# 4_-_Output.net
KiCad netlist of a schematic drawn in Altium Designer
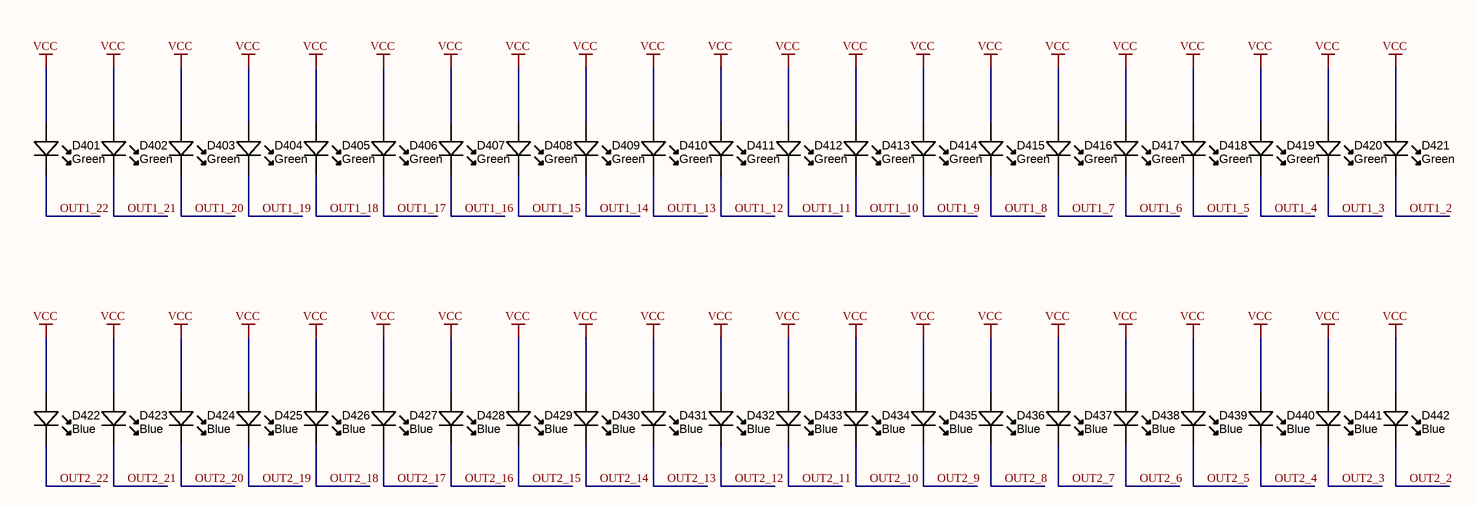
[diagram p0: 4 - Output.SchDoc]

(export (version "E")
  (design (tool "Eeschema 10.0.6"))
  (components
    (comp (ref "D401")
      (value "Green")
      (footprint "LED-0805S-SIDELED-2.1X0.6X1.0")
      (description "LED 0805 SIDELED SMD Green 250mcd 525nm")
      (fields (field (name "COLOR") "Green"))
      (libsource (lib "PBL - Light Sources") (part "LED_SMD_PureGreen_0805RA_250mcd"))
    )
    (comp (ref "D402")
      (value "Green")
      (footprint "LED-0805S-SIDELED-2.1X0.6X1.0")
      (description "LED 0805 SIDELED SMD Green 250mcd 525nm")
      (fields (field (name "COLOR") "Green"))
      (libsource (lib "PBL - Light Sources") (part "LED_SMD_PureGreen_0805RA_250mcd"))
    )
    (comp (ref "D403")
      (value "Green")
      (footprint "LED-0805S-SIDELED-2.1X0.6X1.0")
      (description "LED 0805 SIDELED SMD Green 250mcd 525nm")
      (fields (field (name "COLOR") "Green"))
      (libsource (lib "PBL - Light Sources") (part "LED_SMD_PureGreen_0805RA_250mcd"))
    )
    (comp (ref "D404")
      (value "Green")
      (footprint "LED-0805S-SIDELED-2.1X0.6X1.0")
      (description "LED 0805 SIDELED SMD Green 250mcd 525nm")
      (fields (field (name "COLOR") "Green"))
      (libsource (lib "PBL - Light Sources") (part "LED_SMD_PureGreen_0805RA_250mcd"))
    )
    (comp (ref "D405")
      (value "Green")
      (footprint "LED-0805S-SIDELED-2.1X0.6X1.0")
      (description "LED 0805 SIDELED SMD Green 250mcd 525nm")
      (fields (field (name "COLOR") "Green"))
      (libsource (lib "PBL - Light Sources") (part "LED_SMD_PureGreen_0805RA_250mcd"))
    )
    (comp (ref "D406")
      (value "Green")
      (footprint "LED-0805S-SIDELED-2.1X0.6X1.0")
      (description "LED 0805 SIDELED SMD Green 250mcd 525nm")
      (fields (field (name "COLOR") "Green"))
      (libsource (lib "PBL - Light Sources") (part "LED_SMD_PureGreen_0805RA_250mcd"))
    )
    (comp (ref "D407")
      (value "Green")
      (footprint "LED-0805S-SIDELED-2.1X0.6X1.0")
      (description "LED 0805 SIDELED SMD Green 250mcd 525nm")
      (fields (field (name "COLOR") "Green"))
      (libsource (lib "PBL - Light Sources") (part "LED_SMD_PureGreen_0805RA_250mcd"))
    )
    (comp (ref "D408")
      (value "Green")
      (footprint "LED-0805S-SIDELED-2.1X0.6X1.0")
      (description "LED 0805 SIDELED SMD Green 250mcd 525nm")
      (fields (field (name "COLOR") "Green"))
      (libsource (lib "PBL - Light Sources") (part "LED_SMD_PureGreen_0805RA_250mcd"))
    )
    (comp (ref "D409")
      (value "Green")
      (footprint "LED-0805S-SIDELED-2.1X0.6X1.0")
      (description "LED 0805 SIDELED SMD Green 250mcd 525nm")
      (fields (field (name "COLOR") "Green"))
      (libsource (lib "PBL - Light Sources") (part "LED_SMD_PureGreen_0805RA_250mcd"))
    )
    (comp (ref "D410")
      (value "Green")
      (footprint "LED-0805S-SIDELED-2.1X0.6X1.0")
      (description "LED 0805 SIDELED SMD Green 250mcd 525nm")
      (fields (field (name "COLOR") "Green"))
      (libsource (lib "PBL - Light Sources") (part "LED_SMD_PureGreen_0805RA_250mcd"))
    )
    (comp (ref "D411")
      (value "Green")
      (footprint "LED-0805S-SIDELED-2.1X0.6X1.0")
      (description "LED 0805 SIDELED SMD Green 250mcd 525nm")
      (fields (field (name "COLOR") "Green"))
      (libsource (lib "PBL - Light Sources") (part "LED_SMD_PureGreen_0805RA_250mcd"))
    )
    (comp (ref "D412")
      (value "Green")
      (footprint "LED-0805S-SIDELED-2.1X0.6X1.0")
      (description "LED 0805 SIDELED SMD Green 250mcd 525nm")
      (fields (field (name "COLOR") "Green"))
      (libsource (lib "PBL - Light Sources") (part "LED_SMD_PureGreen_0805RA_250mcd"))
    )
    (comp (ref "D413")
      (value "Green")
      (footprint "LED-0805S-SIDELED-2.1X0.6X1.0")
      (description "LED 0805 SIDELED SMD Green 250mcd 525nm")
      (fields (field (name "COLOR") "Green"))
      (libsource (lib "PBL - Light Sources") (part "LED_SMD_PureGreen_0805RA_250mcd"))
    )
    (comp (ref "D414")
      (value "Green")
      (footprint "LED-0805S-SIDELED-2.1X0.6X1.0")
      (description "LED 0805 SIDELED SMD Green 250mcd 525nm")
      (fields (field (name "COLOR") "Green"))
      (libsource (lib "PBL - Light Sources") (part "LED_SMD_PureGreen_0805RA_250mcd"))
    )
    (comp (ref "D415")
      (value "Green")
      (footprint "LED-0805S-SIDELED-2.1X0.6X1.0")
      (description "LED 0805 SIDELED SMD Green 250mcd 525nm")
      (fields (field (name "COLOR") "Green"))
      (libsource (lib "PBL - Light Sources") (part "LED_SMD_PureGreen_0805RA_250mcd"))
    )
    (comp (ref "D416")
      (value "Green")
      (footprint "LED-0805S-SIDELED-2.1X0.6X1.0")
      (description "LED 0805 SIDELED SMD Green 250mcd 525nm")
      (fields (field (name "COLOR") "Green"))
      (libsource (lib "PBL - Light Sources") (part "LED_SMD_PureGreen_0805RA_250mcd"))
    )
    (comp (ref "D417")
      (value "Green")
      (footprint "LED-0805S-SIDELED-2.1X0.6X1.0")
      (description "LED 0805 SIDELED SMD Green 250mcd 525nm")
      (fields (field (name "COLOR") "Green"))
      (libsource (lib "PBL - Light Sources") (part "LED_SMD_PureGreen_0805RA_250mcd"))
    )
    (comp (ref "D418")
      (value "Green")
      (footprint "LED-0805S-SIDELED-2.1X0.6X1.0")
      (description "LED 0805 SIDELED SMD Green 250mcd 525nm")
      (fields (field (name "COLOR") "Green"))
      (libsource (lib "PBL - Light Sources") (part "LED_SMD_PureGreen_0805RA_250mcd"))
    )
    (comp (ref "D419")
      (value "Green")
      (footprint "LED-0805S-SIDELED-2.1X0.6X1.0")
      (description "LED 0805 SIDELED SMD Green 250mcd 525nm")
      (fields (field (name "COLOR") "Green"))
      (libsource (lib "PBL - Light Sources") (part "LED_SMD_PureGreen_0805RA_250mcd"))
    )
    (comp (ref "D420")
      (value "Green")
      (footprint "LED-0805S-SIDELED-2.1X0.6X1.0")
      (description "LED 0805 SIDELED SMD Green 250mcd 525nm")
      (fields (field (name "COLOR") "Green"))
      (libsource (lib "PBL - Light Sources") (part "LED_SMD_PureGreen_0805RA_250mcd"))
    )
    (comp (ref "D421")
      (value "Green")
      (footprint "LED-0805S-SIDELED-2.1X0.6X1.0")
      (description "LED 0805 SIDELED SMD Green 250mcd 525nm")
      (fields (field (name "COLOR") "Green"))
      (libsource (lib "PBL - Light Sources") (part "LED_SMD_PureGreen_0805RA_250mcd"))
    )
    (comp (ref "D422")
      (value "Blue")
      (footprint "LED-0805S-SIDELED-2.1X0.6X1.0")
      (description "LED 0805 SIDELED SMD Green 250mcd 525nm")
      (fields (field (name "COLOR") "Blue"))
      (libsource (lib "PBL - Light Sources") (part "LED_SMD_PureGreen_0805RA_250mcd"))
    )
    (comp (ref "D423")
      (value "Blue")
      (footprint "LED-0805S-SIDELED-2.1X0.6X1.0")
      (description "LED 0805 SIDELED SMD Green 250mcd 525nm")
      (fields (field (name "COLOR") "Blue"))
      (libsource (lib "PBL - Light Sources") (part "LED_SMD_PureGreen_0805RA_250mcd"))
    )
    (comp (ref "D424")
      (value "Blue")
      (footprint "LED-0805S-SIDELED-2.1X0.6X1.0")
      (description "LED 0805 SIDELED SMD Green 250mcd 525nm")
      (fields (field (name "COLOR") "Blue"))
      (libsource (lib "PBL - Light Sources") (part "LED_SMD_PureGreen_0805RA_250mcd"))
    )
    (comp (ref "D425")
      (value "Blue")
      (footprint "LED-0805S-SIDELED-2.1X0.6X1.0")
      (description "LED 0805 SIDELED SMD Green 250mcd 525nm")
      (fields (field (name "COLOR") "Blue"))
      (libsource (lib "PBL - Light Sources") (part "LED_SMD_PureGreen_0805RA_250mcd"))
    )
    (comp (ref "D426")
      (value "Blue")
      (footprint "LED-0805S-SIDELED-2.1X0.6X1.0")
      (description "LED 0805 SIDELED SMD Green 250mcd 525nm")
      (fields (field (name "COLOR") "Blue"))
      (libsource (lib "PBL - Light Sources") (part "LED_SMD_PureGreen_0805RA_250mcd"))
    )
    (comp (ref "D427")
      (value "Blue")
      (footprint "LED-0805S-SIDELED-2.1X0.6X1.0")
      (description "LED 0805 SIDELED SMD Green 250mcd 525nm")
      (fields (field (name "COLOR") "Blue"))
      (libsource (lib "PBL - Light Sources") (part "LED_SMD_PureGreen_0805RA_250mcd"))
    )
    (comp (ref "D428")
      (value "Blue")
      (footprint "LED-0805S-SIDELED-2.1X0.6X1.0")
      (description "LED 0805 SIDELED SMD Green 250mcd 525nm")
      (fields (field (name "COLOR") "Blue"))
      (libsource (lib "PBL - Light Sources") (part "LED_SMD_PureGreen_0805RA_250mcd"))
    )
    (comp (ref "D429")
      (value "Blue")
      (footprint "LED-0805S-SIDELED-2.1X0.6X1.0")
      (description "LED 0805 SIDELED SMD Green 250mcd 525nm")
      (fields (field (name "COLOR") "Blue"))
      (libsource (lib "PBL - Light Sources") (part "LED_SMD_PureGreen_0805RA_250mcd"))
    )
    (comp (ref "D430")
      (value "Blue")
      (footprint "LED-0805S-SIDELED-2.1X0.6X1.0")
      (description "LED 0805 SIDELED SMD Green 250mcd 525nm")
      (fields (field (name "COLOR") "Blue"))
      (libsource (lib "PBL - Light Sources") (part "LED_SMD_PureGreen_0805RA_250mcd"))
    )
    (comp (ref "D431")
      (value "Blue")
      (footprint "LED-0805S-SIDELED-2.1X0.6X1.0")
      (description "LED 0805 SIDELED SMD Green 250mcd 525nm")
      (fields (field (name "COLOR") "Blue"))
      (libsource (lib "PBL - Light Sources") (part "LED_SMD_PureGreen_0805RA_250mcd"))
    )
    (comp (ref "D432")
      (value "Blue")
      (footprint "LED-0805S-SIDELED-2.1X0.6X1.0")
      (description "LED 0805 SIDELED SMD Green 250mcd 525nm")
      (fields (field (name "COLOR") "Blue"))
      (libsource (lib "PBL - Light Sources") (part "LED_SMD_PureGreen_0805RA_250mcd"))
    )
    (comp (ref "D433")
      (value "Blue")
      (footprint "LED-0805S-SIDELED-2.1X0.6X1.0")
      (description "LED 0805 SIDELED SMD Green 250mcd 525nm")
      (fields (field (name "COLOR") "Blue"))
      (libsource (lib "PBL - Light Sources") (part "LED_SMD_PureGreen_0805RA_250mcd"))
    )
    (comp (ref "D434")
      (value "Blue")
      (footprint "LED-0805S-SIDELED-2.1X0.6X1.0")
      (description "LED 0805 SIDELED SMD Green 250mcd 525nm")
      (fields (field (name "COLOR") "Blue"))
      (libsource (lib "PBL - Light Sources") (part "LED_SMD_PureGreen_0805RA_250mcd"))
    )
    (comp (ref "D435")
      (value "Blue")
      (footprint "LED-0805S-SIDELED-2.1X0.6X1.0")
      (description "LED 0805 SIDELED SMD Green 250mcd 525nm")
      (fields (field (name "COLOR") "Blue"))
      (libsource (lib "PBL - Light Sources") (part "LED_SMD_PureGreen_0805RA_250mcd"))
    )
    (comp (ref "D436")
      (value "Blue")
      (footprint "LED-0805S-SIDELED-2.1X0.6X1.0")
      (description "LED 0805 SIDELED SMD Green 250mcd 525nm")
      (fields (field (name "COLOR") "Blue"))
      (libsource (lib "PBL - Light Sources") (part "LED_SMD_PureGreen_0805RA_250mcd"))
    )
    (comp (ref "D437")
      (value "Blue")
      (footprint "LED-0805S-SIDELED-2.1X0.6X1.0")
      (description "LED 0805 SIDELED SMD Green 250mcd 525nm")
      (fields (field (name "COLOR") "Blue"))
      (libsource (lib "PBL - Light Sources") (part "LED_SMD_PureGreen_0805RA_250mcd"))
    )
    (comp (ref "D438")
      (value "Blue")
      (footprint "LED-0805S-SIDELED-2.1X0.6X1.0")
      (description "LED 0805 SIDELED SMD Green 250mcd 525nm")
      (fields (field (name "COLOR") "Blue"))
      (libsource (lib "PBL - Light Sources") (part "LED_SMD_PureGreen_0805RA_250mcd"))
    )
    (comp (ref "D439")
      (value "Blue")
      (footprint "LED-0805S-SIDELED-2.1X0.6X1.0")
      (description "LED 0805 SIDELED SMD Green 250mcd 525nm")
      (fields (field (name "COLOR") "Blue"))
      (libsource (lib "PBL - Light Sources") (part "LED_SMD_PureGreen_0805RA_250mcd"))
    )
    (comp (ref "D440")
      (value "Blue")
      (footprint "LED-0805S-SIDELED-2.1X0.6X1.0")
      (description "LED 0805 SIDELED SMD Green 250mcd 525nm")
      (fields (field (name "COLOR") "Blue"))
      (libsource (lib "PBL - Light Sources") (part "LED_SMD_PureGreen_0805RA_250mcd"))
    )
    (comp (ref "D441")
      (value "Blue")
      (footprint "LED-0805S-SIDELED-2.1X0.6X1.0")
      (description "LED 0805 SIDELED SMD Green 250mcd 525nm")
      (fields (field (name "COLOR") "Blue"))
      (libsource (lib "PBL - Light Sources") (part "LED_SMD_PureGreen_0805RA_250mcd"))
    )
    (comp (ref "D442")
      (value "Blue")
      (footprint "LED-0805S-SIDELED-2.1X0.6X1.0")
      (description "LED 0805 SIDELED SMD Green 250mcd 525nm")
      (fields (field (name "COLOR") "Blue"))
      (libsource (lib "PBL - Light Sources") (part "LED_SMD_PureGreen_0805RA_250mcd"))
    )
  )
  (nets
    (net (code "1") (name "/OUT1_2") (class "Default")
      (node (ref "D421") (pin "K") (pinfunction "K_K") (pintype "passive"))
    )
    (net (code "2") (name "/OUT1_3") (class "Default")
      (node (ref "D420") (pin "K") (pinfunction "K_K") (pintype "passive"))
    )
    (net (code "3") (name "/OUT1_4") (class "Default")
      (node (ref "D419") (pin "K") (pinfunction "K_K") (pintype "passive"))
    )
    (net (code "4") (name "/OUT1_5") (class "Default")
      (node (ref "D418") (pin "K") (pinfunction "K_K") (pintype "passive"))
    )
    (net (code "5") (name "/OUT1_6") (class "Default")
      (node (ref "D417") (pin "K") (pinfunction "K_K") (pintype "passive"))
    )
    (net (code "6") (name "/OUT1_7") (class "Default")
      (node (ref "D416") (pin "K") (pinfunction "K_K") (pintype "passive"))
    )
    (net (code "7") (name "/OUT1_8") (class "Default")
      (node (ref "D415") (pin "K") (pinfunction "K_K") (pintype "passive"))
    )
    (net (code "8") (name "/OUT1_9") (class "Default")
      (node (ref "D414") (pin "K") (pinfunction "K_K") (pintype "passive"))
    )
    (net (code "9") (name "/OUT1_10") (class "Default")
      (node (ref "D413") (pin "K") (pinfunction "K_K") (pintype "passive"))
    )
    (net (code "10") (name "/OUT1_11") (class "Default")
      (node (ref "D412") (pin "K") (pinfunction "K_K") (pintype "passive"))
    )
    (net (code "11") (name "/OUT1_12") (class "Default")
      (node (ref "D411") (pin "K") (pinfunction "K_K") (pintype "passive"))
    )
    (net (code "12") (name "/OUT1_13") (class "Default")
      (node (ref "D410") (pin "K") (pinfunction "K_K") (pintype "passive"))
    )
    (net (code "13") (name "/OUT1_14") (class "Default")
      (node (ref "D409") (pin "K") (pinfunction "K_K") (pintype "passive"))
    )
    (net (code "14") (name "/OUT1_15") (class "Default")
      (node (ref "D408") (pin "K") (pinfunction "K_K") (pintype "passive"))
    )
    (net (code "15") (name "/OUT1_16") (class "Default")
      (node (ref "D407") (pin "K") (pinfunction "K_K") (pintype "passive"))
    )
    (net (code "16") (name "/OUT1_17") (class "Default")
      (node (ref "D406") (pin "K") (pinfunction "K_K") (pintype "passive"))
    )
    (net (code "17") (name "/OUT1_18") (class "Default")
      (node (ref "D405") (pin "K") (pinfunction "K_K") (pintype "passive"))
    )
    (net (code "18") (name "/OUT1_19") (class "Default")
      (node (ref "D404") (pin "K") (pinfunction "K_K") (pintype "passive"))
    )
    (net (code "19") (name "/OUT1_20") (class "Default")
      (node (ref "D403") (pin "K") (pinfunction "K_K") (pintype "passive"))
    )
    (net (code "20") (name "/OUT1_21") (class "Default")
      (node (ref "D402") (pin "K") (pinfunction "K_K") (pintype "passive"))
    )
    (net (code "21") (name "/OUT1_22") (class "Default")
      (node (ref "D401") (pin "K") (pinfunction "K_K") (pintype "passive"))
    )
    (net (code "22") (name "/OUT2_2") (class "Default")
      (node (ref "D442") (pin "K") (pinfunction "K_K") (pintype "passive"))
    )
    (net (code "23") (name "/OUT2_3") (class "Default")
      (node (ref "D441") (pin "K") (pinfunction "K_K") (pintype "passive"))
    )
    (net (code "24") (name "/OUT2_4") (class "Default")
      (node (ref "D440") (pin "K") (pinfunction "K_K") (pintype "passive"))
    )
    (net (code "25") (name "/OUT2_5") (class "Default")
      (node (ref "D439") (pin "K") (pinfunction "K_K") (pintype "passive"))
    )
    (net (code "26") (name "/OUT2_6") (class "Default")
      (node (ref "D438") (pin "K") (pinfunction "K_K") (pintype "passive"))
    )
    (net (code "27") (name "/OUT2_7") (class "Default")
      (node (ref "D437") (pin "K") (pinfunction "K_K") (pintype "passive"))
    )
    (net (code "28") (name "/OUT2_8") (class "Default")
      (node (ref "D436") (pin "K") (pinfunction "K_K") (pintype "passive"))
    )
    (net (code "29") (name "/OUT2_9") (class "Default")
      (node (ref "D435") (pin "K") (pinfunction "K_K") (pintype "passive"))
    )
    (net (code "30") (name "/OUT2_10") (class "Default")
      (node (ref "D434") (pin "K") (pinfunction "K_K") (pintype "passive"))
    )
    (net (code "31") (name "/OUT2_11") (class "Default")
      (node (ref "D433") (pin "K") (pinfunction "K_K") (pintype "passive"))
    )
    (net (code "32") (name "/OUT2_12") (class "Default")
      (node (ref "D432") (pin "K") (pinfunction "K_K") (pintype "passive"))
    )
    (net (code "33") (name "/OUT2_13") (class "Default")
      (node (ref "D431") (pin "K") (pinfunction "K_K") (pintype "passive"))
    )
    (net (code "34") (name "/OUT2_14") (class "Default")
      (node (ref "D430") (pin "K") (pinfunction "K_K") (pintype "passive"))
    )
    (net (code "35") (name "/OUT2_15") (class "Default")
      (node (ref "D429") (pin "K") (pinfunction "K_K") (pintype "passive"))
    )
    (net (code "36") (name "/OUT2_16") (class "Default")
      (node (ref "D428") (pin "K") (pinfunction "K_K") (pintype "passive"))
    )
    (net (code "37") (name "/OUT2_17") (class "Default")
      (node (ref "D427") (pin "K") (pinfunction "K_K") (pintype "passive"))
    )
    (net (code "38") (name "/OUT2_18") (class "Default")
      (node (ref "D426") (pin "K") (pinfunction "K_K") (pintype "passive"))
    )
    (net (code "39") (name "/OUT2_19") (class "Default")
      (node (ref "D425") (pin "K") (pinfunction "K_K") (pintype "passive"))
    )
    (net (code "40") (name "/OUT2_20") (class "Default")
      (node (ref "D424") (pin "K") (pinfunction "K_K") (pintype "passive"))
    )
    (net (code "41") (name "/OUT2_21") (class "Default")
      (node (ref "D423") (pin "K") (pinfunction "K_K") (pintype "passive"))
    )
    (net (code "42") (name "/OUT2_22") (class "Default")
      (node (ref "D422") (pin "K") (pinfunction "K_K") (pintype "passive"))
    )
    (net (code "43") (name "VCC") (class "Default")
      (node (ref "D401") (pin "A") (pinfunction "A_A") (pintype "passive"))
      (node (ref "D402") (pin "A") (pinfunction "A_A") (pintype "passive"))
      (node (ref "D403") (pin "A") (pinfunction "A_A") (pintype "passive"))
      (node (ref "D404") (pin "A") (pinfunction "A_A") (pintype "passive"))
      (node (ref "D405") (pin "A") (pinfunction "A_A") (pintype "passive"))
      (node (ref "D406") (pin "A") (pinfunction "A_A") (pintype "passive"))
      (node (ref "D407") (pin "A") (pinfunction "A_A") (pintype "passive"))
      (node (ref "D408") (pin "A") (pinfunction "A_A") (pintype "passive"))
      (node (ref "D409") (pin "A") (pinfunction "A_A") (pintype "passive"))
      (node (ref "D410") (pin "A") (pinfunction "A_A") (pintype "passive"))
      (node (ref "D411") (pin "A") (pinfunction "A_A") (pintype "passive"))
      (node (ref "D412") (pin "A") (pinfunction "A_A") (pintype "passive"))
      (node (ref "D413") (pin "A") (pinfunction "A_A") (pintype "passive"))
      (node (ref "D414") (pin "A") (pinfunction "A_A") (pintype "passive"))
      (node (ref "D415") (pin "A") (pinfunction "A_A") (pintype "passive"))
      (node (ref "D416") (pin "A") (pinfunction "A_A") (pintype "passive"))
      (node (ref "D417") (pin "A") (pinfunction "A_A") (pintype "passive"))
      (node (ref "D418") (pin "A") (pinfunction "A_A") (pintype "passive"))
      (node (ref "D419") (pin "A") (pinfunction "A_A") (pintype "passive"))
      (node (ref "D420") (pin "A") (pinfunction "A_A") (pintype "passive"))
      (node (ref "D421") (pin "A") (pinfunction "A_A") (pintype "passive"))
      (node (ref "D422") (pin "A") (pinfunction "A_A") (pintype "passive"))
      (node (ref "D423") (pin "A") (pinfunction "A_A") (pintype "passive"))
      (node (ref "D424") (pin "A") (pinfunction "A_A") (pintype "passive"))
      (node (ref "D425") (pin "A") (pinfunction "A_A") (pintype "passive"))
      (node (ref "D426") (pin "A") (pinfunction "A_A") (pintype "passive"))
      (node (ref "D427") (pin "A") (pinfunction "A_A") (pintype "passive"))
      (node (ref "D428") (pin "A") (pinfunction "A_A") (pintype "passive"))
      (node (ref "D429") (pin "A") (pinfunction "A_A") (pintype "passive"))
      (node (ref "D430") (pin "A") (pinfunction "A_A") (pintype "passive"))
      (node (ref "D431") (pin "A") (pinfunction "A_A") (pintype "passive"))
      (node (ref "D432") (pin "A") (pinfunction "A_A") (pintype "passive"))
      (node (ref "D433") (pin "A") (pinfunction "A_A") (pintype "passive"))
      (node (ref "D434") (pin "A") (pinfunction "A_A") (pintype "passive"))
      (node (ref "D435") (pin "A") (pinfunction "A_A") (pintype "passive"))
      (node (ref "D436") (pin "A") (pinfunction "A_A") (pintype "passive"))
      (node (ref "D437") (pin "A") (pinfunction "A_A") (pintype "passive"))
      (node (ref "D438") (pin "A") (pinfunction "A_A") (pintype "passive"))
      (node (ref "D439") (pin "A") (pinfunction "A_A") (pintype "passive"))
      (node (ref "D440") (pin "A") (pinfunction "A_A") (pintype "passive"))
      (node (ref "D441") (pin "A") (pinfunction "A_A") (pintype "passive"))
      (node (ref "D442") (pin "A") (pinfunction "A_A") (pintype "passive"))
    )
  )
)
